# imu_node.net
KiCad netlist of a schematic drawn in EAGLE
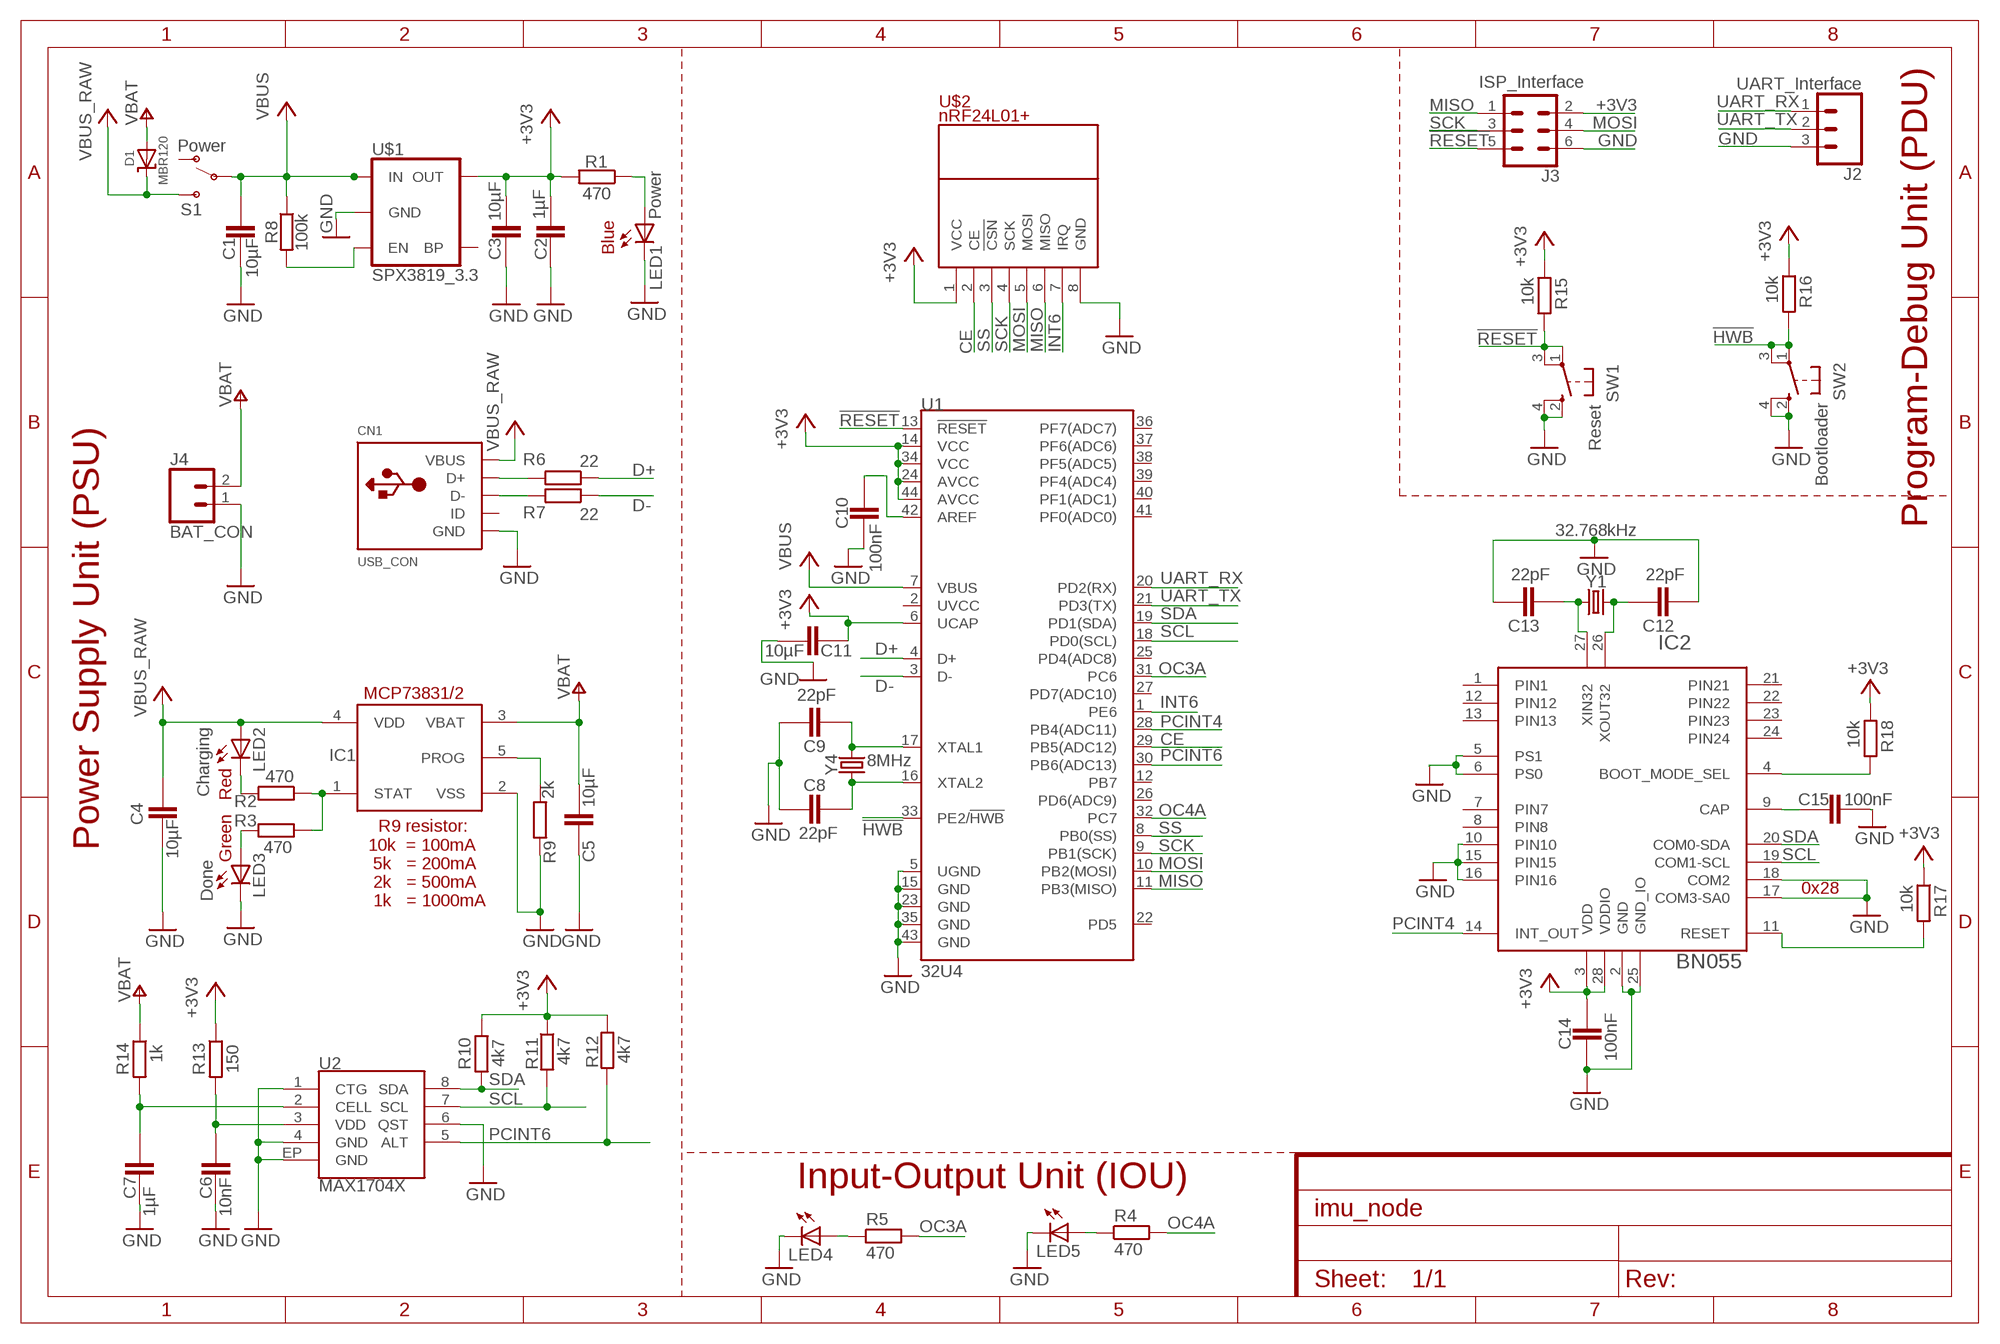
[diagram p0: schematic, sheet 1]

(export (version "E")
  (design (tool "Eeschema 10.0.6"))
  (components
    (comp (ref "C1")
      (value "10µF")
      (footprint "eagle-import:CAPC1608X92N")
      (libsource (lib "eagle-import") (part "CAPACITOR_0603"))
    )
    (comp (ref "C2")
      (value "1µF")
      (footprint "eagle-import:CAPC1608X92N")
      (libsource (lib "eagle-import") (part "CAPACITOR_0603"))
    )
    (comp (ref "C3")
      (value "10µF")
      (footprint "eagle-import:CAPC1608X92N")
      (libsource (lib "eagle-import") (part "CAPACITOR_0603"))
    )
    (comp (ref "C4")
      (value "10µF")
      (footprint "eagle-import:CAPC1608X92N")
      (libsource (lib "eagle-import") (part "CAPACITOR_0603"))
    )
    (comp (ref "C5")
      (value "10µF")
      (footprint "eagle-import:CAPC1608X92N")
      (libsource (lib "eagle-import") (part "CAPACITOR_0603"))
    )
    (comp (ref "C6")
      (value "10nF")
      (footprint "eagle-import:CAPC1608X92N")
      (libsource (lib "eagle-import") (part "CAPACITOR_0603"))
    )
    (comp (ref "C7")
      (value "1µF")
      (footprint "eagle-import:CAPC1608X92N")
      (libsource (lib "eagle-import") (part "CAPACITOR_0603"))
    )
    (comp (ref "C8")
      (value "22pF")
      (footprint "eagle-import:CAPC1608X92N")
      (libsource (lib "eagle-import") (part "CAPACITOR_0603"))
    )
    (comp (ref "C9")
      (value "22pF")
      (footprint "eagle-import:CAPC1608X92N")
      (libsource (lib "eagle-import") (part "CAPACITOR_0603"))
    )
    (comp (ref "C10")
      (value "100nF")
      (footprint "eagle-import:CAPC1608X92N")
      (libsource (lib "eagle-import") (part "CAPACITOR_0603"))
    )
    (comp (ref "C11")
      (value "10µF")
      (footprint "eagle-import:CAPC1608X92N")
      (libsource (lib "eagle-import") (part "CAPACITOR_0603"))
    )
    (comp (ref "C12")
      (value "22pF")
      (footprint "eagle-import:CAPC1608X92N")
      (libsource (lib "eagle-import") (part "CAPACITOR_0603"))
    )
    (comp (ref "C13")
      (value "22pF")
      (footprint "eagle-import:CAPC1608X92N")
      (libsource (lib "eagle-import") (part "CAPACITOR_0603"))
    )
    (comp (ref "C14")
      (value "100nF")
      (footprint "eagle-import:CAPC1608X92N")
      (libsource (lib "eagle-import") (part "CAPACITOR_0603"))
    )
    (comp (ref "C15")
      (value "100nF")
      (footprint "eagle-import:CAPC1608X92N")
      (libsource (lib "eagle-import") (part "CAPACITOR_0603"))
    )
    (comp (ref "CN1")
      (value "USB_CON")
      (footprint "eagle-import:USB-MINIB")
      (libsource (lib "eagle-import") (part "USBMINIB"))
    )
    (comp (ref "D1")
      (value "MBR120")
      (footprint "eagle-import:SOD-123FL")
      (libsource (lib "eagle-import") (part "DIODE_SOD-123FL"))
    )
    (comp (ref "IC1")
      (value "MCP73831/OT")
      (footprint "eagle-import:SOT23-5L")
      (libsource (lib "eagle-import") (part "MCP73831/OT"))
    )
    (comp (ref "IC2")
      (value "BN055")
      (footprint "eagle-import:LGA-28_3.80X5.20_0.5")
      (fields (field (name "PART_NUMBER") "BNO055"))
      (libsource (lib "eagle-import") (part "1658_BNO055"))
    )
    (comp (ref "J2")
      (value "UART_Interface")
      (footprint "eagle-import:1X03")
      (libsource (lib "eagle-import") (part "CONN_03"))
    )
    (comp (ref "J3")
      (value "ISP_Interface")
      (footprint "eagle-import:2X3")
      (libsource (lib "eagle-import") (part "CONN_03X2FEMALE"))
    )
    (comp (ref "J4")
      (value "BAT_CON")
      (footprint "eagle-import:1X02")
      (libsource (lib "eagle-import") (part "CONN_02"))
    )
    (comp (ref "LED1")
      (value "Power")
      (footprint "eagle-import:CHIPLED_0603")
      (libsource (lib "eagle-import") (part "LEDCHIPLED_0603"))
    )
    (comp (ref "LED2")
      (value "Charging")
      (footprint "eagle-import:CHIPLED_0603")
      (libsource (lib "eagle-import") (part "LEDCHIPLED_0603"))
    )
    (comp (ref "LED3")
      (value "Done")
      (footprint "eagle-import:CHIPLED_0603")
      (libsource (lib "eagle-import") (part "LEDCHIPLED_0603"))
    )
    (comp (ref "LED4")
      (value "LEDCHIPLED_0603")
      (footprint "eagle-import:CHIPLED_0603")
      (libsource (lib "eagle-import") (part "LEDCHIPLED_0603"))
    )
    (comp (ref "LED5")
      (value "LEDCHIPLED_0603")
      (footprint "eagle-import:CHIPLED_0603")
      (libsource (lib "eagle-import") (part "LEDCHIPLED_0603"))
    )
    (comp (ref "R1")
      (value "470")
      (footprint "eagle-import:RESC1608X55N")
      (libsource (lib "eagle-import") (part "RESISTOR_0603"))
    )
    (comp (ref "R2")
      (value "470")
      (footprint "eagle-import:RESC1608X55N")
      (libsource (lib "eagle-import") (part "RESISTOR_0603"))
    )
    (comp (ref "R3")
      (value "470")
      (footprint "eagle-import:RESC1608X55N")
      (libsource (lib "eagle-import") (part "RESISTOR_0603"))
    )
    (comp (ref "R4")
      (value "470")
      (footprint "eagle-import:RESC1608X55N")
      (libsource (lib "eagle-import") (part "RESISTOR_0603"))
    )
    (comp (ref "R5")
      (value "470")
      (footprint "eagle-import:RESC1608X55N")
      (libsource (lib "eagle-import") (part "RESISTOR_0603"))
    )
    (comp (ref "R6")
      (value "22")
      (footprint "eagle-import:RESC1608X55N")
      (libsource (lib "eagle-import") (part "RESISTOR_0603"))
    )
    (comp (ref "R7")
      (value "22")
      (footprint "eagle-import:RESC1608X55N")
      (libsource (lib "eagle-import") (part "RESISTOR_0603"))
    )
    (comp (ref "R8")
      (value "100k")
      (footprint "eagle-import:RESC1608X55N")
      (libsource (lib "eagle-import") (part "RESISTOR_0603"))
    )
    (comp (ref "R9")
      (value "2k")
      (footprint "eagle-import:RESC1608X55N")
      (libsource (lib "eagle-import") (part "RESISTOR_0603"))
    )
    (comp (ref "R10")
      (value "4k7")
      (footprint "eagle-import:RESC1608X55N")
      (libsource (lib "eagle-import") (part "RESISTOR_0603"))
    )
    (comp (ref "R11")
      (value "4k7")
      (footprint "eagle-import:RESC1608X55N")
      (libsource (lib "eagle-import") (part "RESISTOR_0603"))
    )
    (comp (ref "R12")
      (value "4k7")
      (footprint "eagle-import:RESC1608X55N")
      (libsource (lib "eagle-import") (part "RESISTOR_0603"))
    )
    (comp (ref "R13")
      (value "150")
      (footprint "eagle-import:RESC1608X55N")
      (libsource (lib "eagle-import") (part "RESISTOR_0603"))
    )
    (comp (ref "R14")
      (value "1k")
      (footprint "eagle-import:RESC1608X55N")
      (libsource (lib "eagle-import") (part "RESISTOR_0603"))
    )
    (comp (ref "R15")
      (value "10k")
      (footprint "eagle-import:RESC1608X55N")
      (libsource (lib "eagle-import") (part "RESISTOR_0603"))
    )
    (comp (ref "R16")
      (value "10k")
      (footprint "eagle-import:RESC1608X55N")
      (libsource (lib "eagle-import") (part "RESISTOR_0603"))
    )
    (comp (ref "R17")
      (value "10k")
      (footprint "eagle-import:RESC1608X55N")
      (libsource (lib "eagle-import") (part "RESISTOR_0603"))
    )
    (comp (ref "R18")
      (value "10k")
      (footprint "eagle-import:RESC1608X55N")
      (libsource (lib "eagle-import") (part "RESISTOR_0603"))
    )
    (comp (ref "S1")
      (value "Power")
      (footprint "eagle-import:SWITCH_SPST_SMD_A")
      (libsource (lib "eagle-import") (part "SWITCH-SPDT-SMD-RIGHT-ANGLE"))
    )
    (comp (ref "SW1")
      (value "Reset")
      (footprint "eagle-import:KMR2")
      (libsource (lib "eagle-import") (part "SPST_TACT-KMR2"))
    )
    (comp (ref "SW2")
      (value "Bootloader")
      (footprint "eagle-import:KMR2")
      (libsource (lib "eagle-import") (part "SPST_TACT-KMR2"))
    )
    (comp (ref "U$1")
      (value "SPX3819_3.3")
      (footprint "eagle-import:SOT23-5")
      (libsource (lib "eagle-import") (part "V_REG_SPX3819-SOT23-5"))
    )
    (comp (ref "U$2")
      (value "nRF24L01+")
      (footprint "eagle-import:6-PIN-BREAKOUT")
      (libsource (lib "eagle-import") (part "6-PIN-BREAKOUT6-PIN-BREAKOUT"))
    )
    (comp (ref "U1")
      (value "32U4")
      (footprint "eagle-import:TQFP44")
      (libsource (lib "eagle-import") (part "ATMEGA32U4TQFP-44"))
    )
    (comp (ref "U2")
      (value "MAX1704X")
      (footprint "eagle-import:TDFN-8")
      (libsource (lib "eagle-import") (part "MAX1704X"))
    )
    (comp (ref "Y1")
      (value "32.768kHz")
      (footprint "eagle-import:CRYSTAL-SMD-3.2X1.5MM")
      (libsource (lib "eagle-import") (part "CRYSTAL-32.768KHZSMD-3.2X1.5"))
    )
    (comp (ref "Y4")
      (value "8MHz")
      (footprint "eagle-import:CRYSTAL-SMD-5X3.2-4PAD")
      (libsource (lib "eagle-import") (part "CRYSTAL-8MHZSMD-5X3.2"))
    )
  )
  (nets
    (net (code "1") (name "+3V3") (class "Default")
      (node (ref "C11") (pin "1") (pinfunction "1_1") (pintype "passive"))
      (node (ref "C14") (pin "1") (pinfunction "1_1") (pintype "passive"))
      (node (ref "C2") (pin "2") (pinfunction "2_2") (pintype "passive"))
      (node (ref "C3") (pin "2") (pinfunction "2_2") (pintype "passive"))
      (node (ref "IC2") (pin "28") (pinfunction "VDDIO_28") (pintype "power_in"))
      (node (ref "IC2") (pin "3") (pinfunction "VDD_3") (pintype "power_in"))
      (node (ref "J3") (pin "2") (pinfunction "2_2") (pintype "bidirectional"))
      (node (ref "R1") (pin "2") (pinfunction "2_2") (pintype "passive"))
      (node (ref "R10") (pin "1") (pinfunction "1_1") (pintype "passive"))
      (node (ref "R11") (pin "1") (pinfunction "1_1") (pintype "passive"))
      (node (ref "R12") (pin "1") (pinfunction "1_1") (pintype "passive"))
      (node (ref "R13") (pin "1") (pinfunction "1_1") (pintype "passive"))
      (node (ref "R15") (pin "1") (pinfunction "1_1") (pintype "passive"))
      (node (ref "R16") (pin "1") (pinfunction "1_1") (pintype "passive"))
      (node (ref "R17") (pin "1") (pinfunction "1_1") (pintype "passive"))
      (node (ref "R18") (pin "1") (pinfunction "1_1") (pintype "passive"))
      (node (ref "U$1") (pin "5") (pinfunction "OUT_5") (pintype "passive"))
      (node (ref "U$2") (pin "1") (pinfunction "VCC_1") (pintype "bidirectional"))
      (node (ref "U1") (pin "14") (pinfunction "VCC_14") (pintype "bidirectional"))
      (node (ref "U1") (pin "24") (pinfunction "AVCC_24") (pintype "bidirectional"))
      (node (ref "U1") (pin "34") (pinfunction "VCC_34") (pintype "bidirectional"))
      (node (ref "U1") (pin "44") (pinfunction "AVCC_44") (pintype "bidirectional"))
      (node (ref "U1") (pin "6") (pinfunction "UCAP_6") (pintype "bidirectional"))
    )
    (net (code "2") (name "/CE") (class "Default")
      (node (ref "U$2") (pin "2") (pinfunction "CE_2") (pintype "bidirectional"))
      (node (ref "U1") (pin "29") (pinfunction "PB5(ADC12)_29") (pintype "bidirectional"))
    )
    (net (code "3") (name "/D+") (class "Default")
      (node (ref "R6") (pin "1") (pinfunction "1_1") (pintype "passive"))
      (node (ref "U1") (pin "4") (pinfunction "D+_4") (pintype "bidirectional"))
    )
    (net (code "4") (name "/D-") (class "Default")
      (node (ref "R7") (pin "1") (pinfunction "1_1") (pintype "passive"))
      (node (ref "U1") (pin "3") (pinfunction "D-_3") (pintype "bidirectional"))
    )
    (net (code "5") (name "/INT6") (class "Default")
      (node (ref "U$2") (pin "7") (pinfunction "IRQ_7") (pintype "bidirectional"))
      (node (ref "U1") (pin "1") (pinfunction "PE6_1") (pintype "bidirectional"))
    )
    (net (code "6") (name "/MISO") (class "Default")
      (node (ref "J3") (pin "1") (pinfunction "1_1") (pintype "bidirectional"))
      (node (ref "U$2") (pin "6") (pinfunction "MISO_6") (pintype "bidirectional"))
      (node (ref "U1") (pin "11") (pinfunction "PB3(MISO)_11") (pintype "bidirectional"))
    )
    (net (code "7") (name "/MOSI") (class "Default")
      (node (ref "J3") (pin "4") (pinfunction "4_4") (pintype "bidirectional"))
      (node (ref "U$2") (pin "5") (pinfunction "MOSI_5") (pintype "bidirectional"))
      (node (ref "U1") (pin "10") (pinfunction "PB2(MOSI)_10") (pintype "bidirectional"))
    )
    (net (code "8") (name "/OC3A") (class "Default")
      (node (ref "R5") (pin "2") (pinfunction "2_2") (pintype "passive"))
      (node (ref "U1") (pin "31") (pinfunction "PC6_31") (pintype "bidirectional"))
    )
    (net (code "9") (name "/OC4A") (class "Default")
      (node (ref "R4") (pin "2") (pinfunction "2_2") (pintype "passive"))
      (node (ref "U1") (pin "32") (pinfunction "PC7_32") (pintype "bidirectional"))
    )
    (net (code "10") (name "/PCINT4") (class "Default")
      (node (ref "IC2") (pin "14") (pinfunction "INT_OUT_14") (pintype "output"))
      (node (ref "U1") (pin "28") (pinfunction "PB4(ADC11)_28") (pintype "bidirectional"))
    )
    (net (code "11") (name "/PCINT6") (class "Default")
      (node (ref "R12") (pin "2") (pinfunction "2_2") (pintype "passive"))
      (node (ref "U1") (pin "30") (pinfunction "PB6(ADC13)_30") (pintype "bidirectional"))
      (node (ref "U2") (pin "5") (pinfunction "ALT_5") (pintype "bidirectional"))
    )
    (net (code "12") (name "/SCK") (class "Default")
      (node (ref "J3") (pin "3") (pinfunction "3_3") (pintype "bidirectional"))
      (node (ref "U$2") (pin "4") (pinfunction "SCK_4") (pintype "bidirectional"))
      (node (ref "U1") (pin "9") (pinfunction "PB1(SCK)_9") (pintype "bidirectional"))
    )
    (net (code "13") (name "/SCL") (class "Default")
      (node (ref "IC2") (pin "19") (pinfunction "COM1-SCL_19") (pintype "bidirectional"))
      (node (ref "R11") (pin "2") (pinfunction "2_2") (pintype "passive"))
      (node (ref "U1") (pin "18") (pinfunction "PD0(SCL)_18") (pintype "bidirectional"))
      (node (ref "U2") (pin "7") (pinfunction "SCL_7") (pintype "bidirectional"))
    )
    (net (code "14") (name "/SDA") (class "Default")
      (node (ref "IC2") (pin "20") (pinfunction "COM0-SDA_20") (pintype "bidirectional"))
      (node (ref "R10") (pin "2") (pinfunction "2_2") (pintype "passive"))
      (node (ref "U1") (pin "19") (pinfunction "PD1(SDA)_19") (pintype "bidirectional"))
      (node (ref "U2") (pin "8") (pinfunction "SDA_8") (pintype "bidirectional"))
    )
    (net (code "15") (name "/SS") (class "Default")
      (node (ref "U$2") (pin "3") (pinfunction "~{CSN}_3") (pintype "bidirectional"))
      (node (ref "U1") (pin "8") (pinfunction "PB0(SS)_8") (pintype "bidirectional"))
    )
    (net (code "16") (name "/UART_RX") (class "Default")
      (node (ref "J2") (pin "1") (pinfunction "1_1") (pintype "passive"))
      (node (ref "U1") (pin "20") (pinfunction "PD2(RX)_20") (pintype "bidirectional"))
    )
    (net (code "17") (name "/UART_TX") (class "Default")
      (node (ref "J2") (pin "2") (pinfunction "2_2") (pintype "passive"))
      (node (ref "U1") (pin "21") (pinfunction "PD3(TX)_21") (pintype "bidirectional"))
    )
    (net (code "18") (name "/~{HWB}") (class "Default")
      (node (ref "R16") (pin "2") (pinfunction "2_2") (pintype "passive"))
      (node (ref "SW2") (pin "1") (pinfunction "P_1") (pintype "passive"))
      (node (ref "SW2") (pin "3") (pinfunction "P1_3") (pintype "passive"))
      (node (ref "U1") (pin "33") (pinfunction "PE2/~{HWB}_33") (pintype "bidirectional"))
    )
    (net (code "19") (name "/~{RESET}") (class "Default")
      (node (ref "J3") (pin "5") (pinfunction "5_5") (pintype "bidirectional"))
      (node (ref "R15") (pin "2") (pinfunction "2_2") (pintype "passive"))
      (node (ref "SW1") (pin "1") (pinfunction "P_1") (pintype "passive"))
      (node (ref "SW1") (pin "3") (pinfunction "P1_3") (pintype "passive"))
      (node (ref "U1") (pin "13") (pinfunction "~{RESET}_13") (pintype "bidirectional"))
    )
    (net (code "20") (name "GND") (class "Default")
      (node (ref "C1") (pin "1") (pinfunction "1_1") (pintype "passive"))
      (node (ref "C10") (pin "2") (pinfunction "2_2") (pintype "passive"))
      (node (ref "C11") (pin "2") (pinfunction "2_2") (pintype "passive"))
      (node (ref "C12") (pin "1") (pinfunction "1_1") (pintype "passive"))
      (node (ref "C13") (pin "2") (pinfunction "2_2") (pintype "passive"))
      (node (ref "C14") (pin "2") (pinfunction "2_2") (pintype "passive"))
      (node (ref "C15") (pin "2") (pinfunction "2_2") (pintype "passive"))
      (node (ref "C2") (pin "1") (pinfunction "1_1") (pintype "passive"))
      (node (ref "C3") (pin "1") (pinfunction "1_1") (pintype "passive"))
      (node (ref "C4") (pin "1") (pinfunction "1_1") (pintype "passive"))
      (node (ref "C5") (pin "1") (pinfunction "1_1") (pintype "passive"))
      (node (ref "C6") (pin "1") (pinfunction "1_1") (pintype "passive"))
      (node (ref "C7") (pin "1") (pinfunction "1_1") (pintype "passive"))
      (node (ref "C8") (pin "2") (pinfunction "2_2") (pintype "passive"))
      (node (ref "C9") (pin "2") (pinfunction "2_2") (pintype "passive"))
      (node (ref "CN1") (pin "GND") (pinfunction "GND_GND") (pintype "power_in"))
      (node (ref "IC1") (pin "2") (pinfunction "VSS_2") (pintype "power_in"))
      (node (ref "IC2") (pin "10") (pinfunction "PIN10_10") (pintype "passive"))
      (node (ref "IC2") (pin "15") (pinfunction "PIN15_15") (pintype "passive"))
      (node (ref "IC2") (pin "16") (pinfunction "PIN16_16") (pintype "passive"))
      (node (ref "IC2") (pin "17") (pinfunction "COM3-SA0_17") (pintype "bidirectional"))
      (node (ref "IC2") (pin "18") (pinfunction "COM2_18") (pintype "bidirectional"))
      (node (ref "IC2") (pin "2") (pinfunction "GND_2") (pintype "power_in"))
      (node (ref "IC2") (pin "25") (pinfunction "GND_IO_25") (pintype "power_in"))
      (node (ref "IC2") (pin "5") (pinfunction "PS1_5") (pintype "input"))
      (node (ref "IC2") (pin "6") (pinfunction "PS0_6") (pintype "input"))
      (node (ref "J2") (pin "3") (pinfunction "3_3") (pintype "passive"))
      (node (ref "J3") (pin "6") (pinfunction "6_6") (pintype "bidirectional"))
      (node (ref "J4") (pin "1") (pinfunction "1_1") (pintype "passive"))
      (node (ref "LED1") (pin "C") (pinfunction "C_C") (pintype "passive"))
      (node (ref "LED3") (pin "C") (pinfunction "C_C") (pintype "passive"))
      (node (ref "LED4") (pin "C") (pinfunction "C_C") (pintype "passive"))
      (node (ref "LED5") (pin "C") (pinfunction "C_C") (pintype "passive"))
      (node (ref "R9") (pin "2") (pinfunction "2_2") (pintype "passive"))
      (node (ref "SW1") (pin "2") (pinfunction "S_2") (pintype "passive"))
      (node (ref "SW1") (pin "4") (pinfunction "S1_4") (pintype "passive"))
      (node (ref "SW2") (pin "2") (pinfunction "S_2") (pintype "passive"))
      (node (ref "SW2") (pin "4") (pinfunction "S1_4") (pintype "passive"))
      (node (ref "U$1") (pin "2") (pinfunction "GND_2") (pintype "input"))
      (node (ref "U$2") (pin "8") (pinfunction "GND_8") (pintype "bidirectional"))
      (node (ref "U1") (pin "15") (pinfunction "GND_15") (pintype "bidirectional"))
      (node (ref "U1") (pin "23") (pinfunction "GND_23") (pintype "bidirectional"))
      (node (ref "U1") (pin "35") (pinfunction "GND_35") (pintype "bidirectional"))
      (node (ref "U1") (pin "43") (pinfunction "GND_43") (pintype "bidirectional"))
      (node (ref "U1") (pin "5") (pinfunction "UGND_5") (pintype "bidirectional"))
      (node (ref "U2") (pin "1") (pinfunction "CTG_1") (pintype "bidirectional"))
      (node (ref "U2") (pin "4") (pinfunction "GND_4") (pintype "bidirectional"))
      (node (ref "U2") (pin "6") (pinfunction "QST_6") (pintype "bidirectional"))
      (node (ref "U2") (pin "EP") (pinfunction "GND_EP") (pintype "bidirectional"))
    )
    (net (code "21") (name "Net-(CN1-PadD+)") (class "Default")
      (node (ref "CN1") (pin "D+") (pinfunction "D+_D+") (pintype "bidirectional"))
      (node (ref "R6") (pin "2") (pinfunction "2_2") (pintype "passive"))
    )
    (net (code "22") (name "Net-(CN1-PadD-)") (class "Default")
      (node (ref "CN1") (pin "D-") (pinfunction "D-_D-") (pintype "bidirectional"))
      (node (ref "R7") (pin "2") (pinfunction "2_2") (pintype "passive"))
    )
    (net (code "23") (name "Net-(IC1-PROG)") (class "Default")
      (node (ref "IC1") (pin "5") (pinfunction "PROG_5") (pintype "input"))
      (node (ref "R9") (pin "1") (pinfunction "1_1") (pintype "passive"))
    )
    (net (code "24") (name "Net-(IC1-STAT)") (class "Default")
      (node (ref "IC1") (pin "1") (pinfunction "STAT_1") (pintype "output"))
      (node (ref "R2") (pin "1") (pinfunction "1_1") (pintype "passive"))
      (node (ref "R3") (pin "1") (pinfunction "1_1") (pintype "passive"))
    )
    (net (code "25") (name "Net-(IC2-BOOT_MODE_SEL)") (class "Default")
      (node (ref "IC2") (pin "4") (pinfunction "BOOT_MODE_SEL_4") (pintype "input"))
      (node (ref "R18") (pin "2") (pinfunction "2_2") (pintype "passive"))
    )
    (net (code "26") (name "Net-(IC2-CAP)") (class "Default")
      (node (ref "C15") (pin "1") (pinfunction "1_1") (pintype "passive"))
      (node (ref "IC2") (pin "9") (pinfunction "CAP_9") (pintype "tri_state"))
    )
    (net (code "27") (name "Net-(IC2-RESET)") (class "Default")
      (node (ref "IC2") (pin "11") (pinfunction "RESET_11") (pintype "input"))
      (node (ref "R17") (pin "2") (pinfunction "2_2") (pintype "passive"))
    )
    (net (code "28") (name "Net-(IC2-XIN32)") (class "Default")
      (node (ref "C13") (pin "1") (pinfunction "1_1") (pintype "passive"))
      (node (ref "IC2") (pin "27") (pinfunction "XIN32_27") (pintype "bidirectional"))
      (node (ref "Y1") (pin "P$1") (pinfunction "1_P$1") (pintype "passive"))
    )
    (net (code "29") (name "Net-(IC2-XOUT32)") (class "Default")
      (node (ref "C12") (pin "2") (pinfunction "2_2") (pintype "passive"))
      (node (ref "IC2") (pin "26") (pinfunction "XOUT32_26") (pintype "output"))
      (node (ref "Y1") (pin "P$2") (pinfunction "2_P$2") (pintype "passive"))
    )
    (net (code "30") (name "Net-(LED1-PadA)") (class "Default")
      (node (ref "LED1") (pin "A") (pinfunction "A_A") (pintype "passive"))
      (node (ref "R1") (pin "1") (pinfunction "1_1") (pintype "passive"))
    )
    (net (code "31") (name "Net-(LED2-PadC)") (class "Default")
      (node (ref "LED2") (pin "C") (pinfunction "C_C") (pintype "passive"))
      (node (ref "R2") (pin "2") (pinfunction "2_2") (pintype "passive"))
    )
    (net (code "32") (name "Net-(LED3-PadA)") (class "Default")
      (node (ref "LED3") (pin "A") (pinfunction "A_A") (pintype "passive"))
      (node (ref "R3") (pin "2") (pinfunction "2_2") (pintype "passive"))
    )
    (net (code "33") (name "Net-(LED4-PadA)") (class "Default")
      (node (ref "LED4") (pin "A") (pinfunction "A_A") (pintype "passive"))
      (node (ref "R5") (pin "1") (pinfunction "1_1") (pintype "passive"))
    )
    (net (code "34") (name "Net-(LED5-PadA)") (class "Default")
      (node (ref "LED5") (pin "A") (pinfunction "A_A") (pintype "passive"))
      (node (ref "R4") (pin "1") (pinfunction "1_1") (pintype "passive"))
    )
    (net (code "35") (name "Net-(U$1-EN)") (class "Default")
      (node (ref "R8") (pin "2") (pinfunction "2_2") (pintype "passive"))
      (node (ref "U$1") (pin "3") (pinfunction "EN_3") (pintype "input"))
    )
    (net (code "36") (name "Net-(U1-AREF)") (class "Default")
      (node (ref "C10") (pin "1") (pinfunction "1_1") (pintype "passive"))
      (node (ref "U1") (pin "42") (pinfunction "AREF_42") (pintype "bidirectional"))
    )
    (net (code "37") (name "Net-(U1-XTAL1)") (class "Default")
      (node (ref "C9") (pin "1") (pinfunction "1_1") (pintype "passive"))
      (node (ref "U1") (pin "17") (pinfunction "XTAL1_17") (pintype "bidirectional"))
      (node (ref "Y4") (pin "3") (pinfunction "2_3") (pintype "passive"))
    )
    (net (code "38") (name "Net-(U1-XTAL2)") (class "Default")
      (node (ref "C8") (pin "1") (pinfunction "1_1") (pintype "passive"))
      (node (ref "U1") (pin "16") (pinfunction "XTAL2_16") (pintype "bidirectional"))
      (node (ref "Y4") (pin "1") (pinfunction "1_1") (pintype "passive"))
    )
    (net (code "39") (name "Net-(U2-CELL)") (class "Default")
      (node (ref "C7") (pin "2") (pinfunction "2_2") (pintype "passive"))
      (node (ref "R14") (pin "2") (pinfunction "2_2") (pintype "passive"))
      (node (ref "U2") (pin "2") (pinfunction "CELL_2") (pintype "bidirectional"))
    )
    (net (code "40") (name "Net-(U2-VDD)") (class "Default")
      (node (ref "C6") (pin "2") (pinfunction "2_2") (pintype "passive"))
      (node (ref "R13") (pin "2") (pinfunction "2_2") (pintype "passive"))
      (node (ref "U2") (pin "3") (pinfunction "VDD_3") (pintype "bidirectional"))
    )
    (net (code "41") (name "VBAT") (class "Default")
      (node (ref "C5") (pin "2") (pinfunction "2_2") (pintype "passive"))
      (node (ref "D1") (pin "A") (pinfunction "A_A") (pintype "passive"))
      (node (ref "IC1") (pin "3") (pinfunction "VBAT_3") (pintype "bidirectional"))
      (node (ref "J4") (pin "2") (pinfunction "2_2") (pintype "passive"))
      (node (ref "R14") (pin "1") (pinfunction "1_1") (pintype "passive"))
    )
    (net (code "42") (name "VBUS") (class "Default")
      (node (ref "C1") (pin "2") (pinfunction "2_2") (pintype "passive"))
      (node (ref "R8") (pin "1") (pinfunction "1_1") (pintype "passive"))
      (node (ref "S1") (pin "2") (pinfunction "P_2") (pintype "passive"))
      (node (ref "U$1") (pin "1") (pinfunction "IN_1") (pintype "input"))
      (node (ref "U1") (pin "7") (pinfunction "VBUS_7") (pintype "bidirectional"))
    )
    (net (code "43") (name "VBUS_RAW") (class "Default")
      (node (ref "C4") (pin "2") (pinfunction "2_2") (pintype "passive"))
      (node (ref "CN1") (pin "VBUS") (pinfunction "VBUS_VBUS") (pintype "power_in"))
      (node (ref "D1") (pin "C") (pinfunction "C_C") (pintype "passive"))
      (node (ref "IC1") (pin "4") (pinfunction "VDD_4") (pintype "power_in"))
      (node (ref "LED2") (pin "A") (pinfunction "A_A") (pintype "passive"))
      (node (ref "S1") (pin "3") (pinfunction "S_3") (pintype "passive"))
    )
    (net (code "44") (name "unconnected-(CN1-PadID)") (class "Default")
      (node (ref "CN1") (pin "ID") (pinfunction "ID_ID") (pintype "bidirectional"))
    )
    (net (code "45") (name "unconnected-(IC2-PIN1-Pad1)") (class "Default")
      (node (ref "IC2") (pin "1") (pinfunction "PIN1_1") (pintype "no_connect"))
    )
    (net (code "46") (name "unconnected-(IC2-PIN7-Pad7)") (class "Default")
      (node (ref "IC2") (pin "7") (pinfunction "PIN7_7") (pintype "tri_state"))
    )
    (net (code "47") (name "unconnected-(IC2-PIN8-Pad8)") (class "Default")
      (node (ref "IC2") (pin "8") (pinfunction "PIN8_8") (pintype "tri_state"))
    )
    (net (code "48") (name "unconnected-(IC2-PIN12-Pad12)") (class "Default")
      (node (ref "IC2") (pin "12") (pinfunction "PIN12_12") (pintype "passive"))
    )
    (net (code "49") (name "unconnected-(IC2-PIN13-Pad13)") (class "Default")
      (node (ref "IC2") (pin "13") (pinfunction "PIN13_13") (pintype "passive"))
    )
    (net (code "50") (name "unconnected-(IC2-PIN21-Pad21)") (class "Default")
      (node (ref "IC2") (pin "21") (pinfunction "PIN21_21") (pintype "passive"))
    )
    (net (code "51") (name "unconnected-(IC2-PIN22-Pad22)") (class "Default")
      (node (ref "IC2") (pin "22") (pinfunction "PIN22_22") (pintype "passive"))
    )
    (net (code "52") (name "unconnected-(IC2-PIN23-Pad23)") (class "Default")
      (node (ref "IC2") (pin "23") (pinfunction "PIN23_23") (pintype "passive"))
    )
    (net (code "53") (name "unconnected-(IC2-PIN24-Pad24)") (class "Default")
      (node (ref "IC2") (pin "24") (pinfunction "PIN24_24") (pintype "passive"))
    )
    (net (code "54") (name "unconnected-(S1-O-Pad1)") (class "Default")
      (node (ref "S1") (pin "1") (pinfunction "O_1") (pintype "passive"))
    )
    (net (code "55") (name "unconnected-(U$1-BP-Pad4)") (class "Default")
      (node (ref "U$1") (pin "4") (pinfunction "BP_4") (pintype "input"))
    )
    (net (code "56") (name "unconnected-(U1-PB7-Pad12)") (class "Default")
      (node (ref "U1") (pin "12") (pinfunction "PB7_12") (pintype "bidirectional"))
    )
    (net (code "57") (name "unconnected-(U1-PD4(ADC8)-Pad25)") (class "Default")
      (node (ref "U1") (pin "25") (pinfunction "PD4(ADC8)_25") (pintype "bidirectional"))
    )
    (net (code "58") (name "unconnected-(U1-PD5-Pad22)") (class "Default")
      (node (ref "U1") (pin "22") (pinfunction "PD5_22") (pintype "bidirectional"))
    )
    (net (code "59") (name "unconnected-(U1-PD6(ADC9)-Pad26)") (class "Default")
      (node (ref "U1") (pin "26") (pinfunction "PD6(ADC9)_26") (pintype "bidirectional"))
    )
    (net (code "60") (name "unconnected-(U1-PD7(ADC10)-Pad27)") (class "Default")
      (node (ref "U1") (pin "27") (pinfunction "PD7(ADC10)_27") (pintype "bidirectional"))
    )
    (net (code "61") (name "unconnected-(U1-PF0(ADC0)-Pad41)") (class "Default")
      (node (ref "U1") (pin "41") (pinfunction "PF0(ADC0)_41") (pintype "bidirectional"))
    )
    (net (code "62") (name "unconnected-(U1-PF1(ADC1)-Pad40)") (class "Default")
      (node (ref "U1") (pin "40") (pinfunction "PF1(ADC1)_40") (pintype "bidirectional"))
    )
    (net (code "63") (name "unconnected-(U1-PF4(ADC4)-Pad39)") (class "Default")
      (node (ref "U1") (pin "39") (pinfunction "PF4(ADC4)_39") (pintype "bidirectional"))
    )
    (net (code "64") (name "unconnected-(U1-PF5(ADC5)-Pad38)") (class "Default")
      (node (ref "U1") (pin "38") (pinfunction "PF5(ADC5)_38") (pintype "bidirectional"))
    )
    (net (code "65") (name "unconnected-(U1-PF6(ADC6)-Pad37)") (class "Default")
      (node (ref "U1") (pin "37") (pinfunction "PF6(ADC6)_37") (pintype "bidirectional"))
    )
    (net (code "66") (name "unconnected-(U1-PF7(ADC7)-Pad36)") (class "Default")
      (node (ref "U1") (pin "36") (pinfunction "PF7(ADC7)_36") (pintype "bidirectional"))
    )
    (net (code "67") (name "unconnected-(U1-UVCC-Pad2)") (class "Default")
      (node (ref "U1") (pin "2") (pinfunction "UVCC_2") (pintype "bidirectional"))
    )
  )
)
